# DCDCreg.net
KiCad netlist of a schematic drawn in Altium Designer
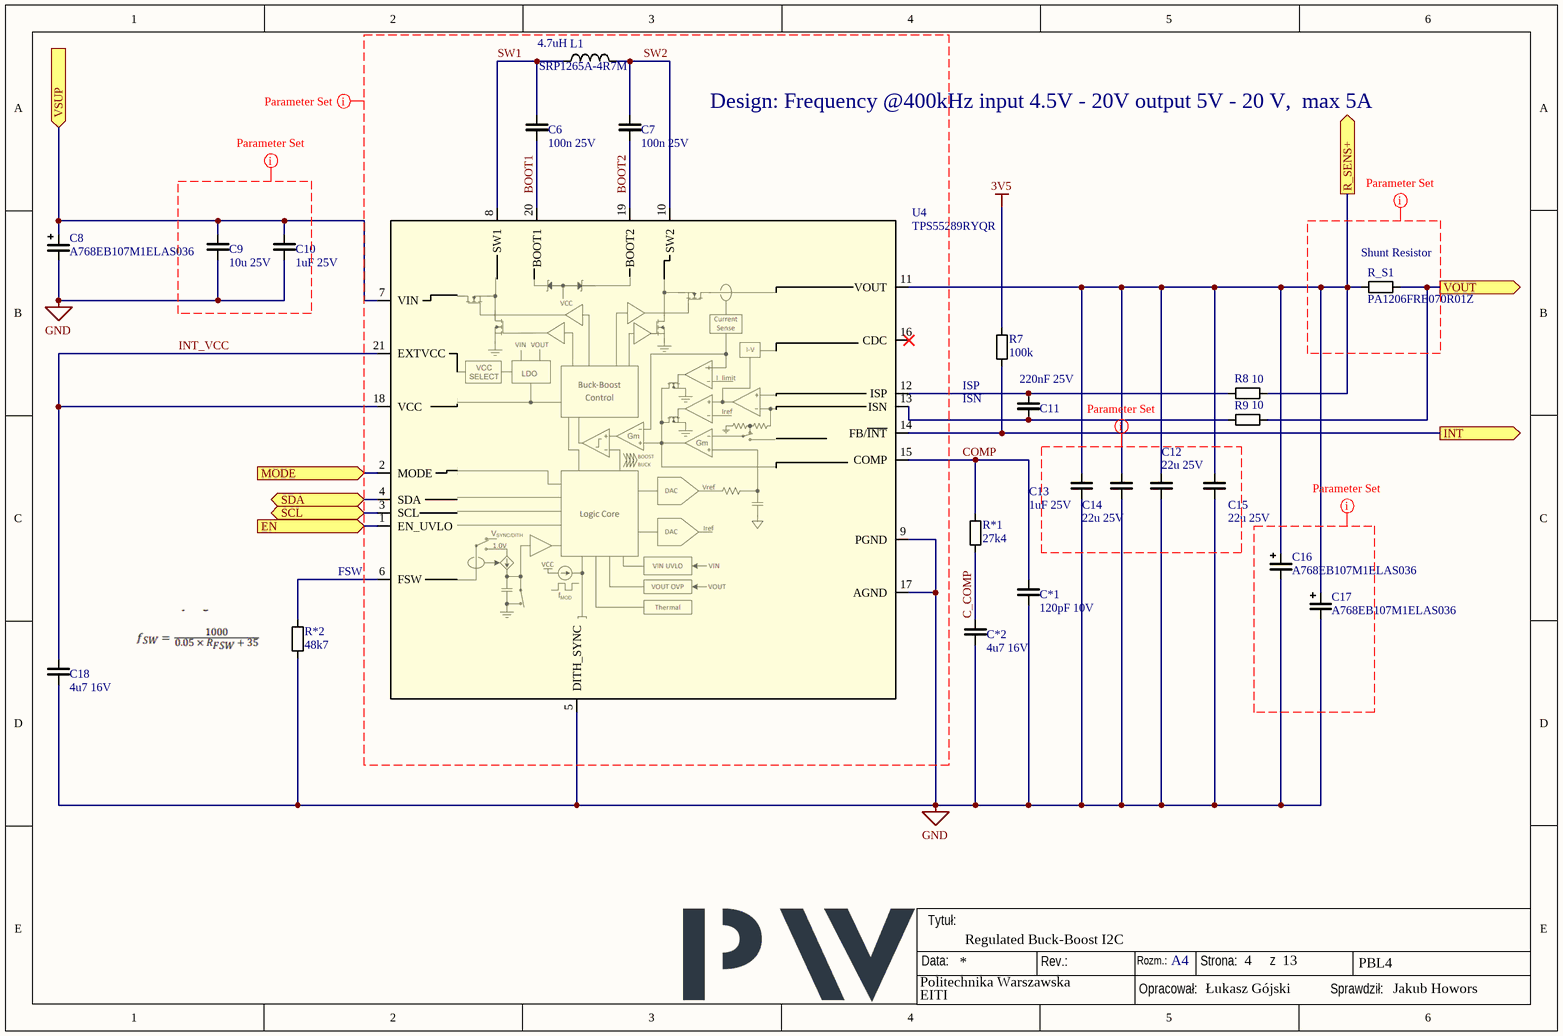
[diagram p0: DCDCreg.SchDoc]

(export (version "E")
  (design (tool "Eeschema 10.0.6"))
  (components
    (comp (ref "C*1")
      (value "120pF 10V")
      (footprint "C_0603")
      (description "Ceramic capacitor")
      (fields (field (name "VOLTAGE") "10V") (field (name "TOLERANCE") "10%"))
      (libsource (lib "Common") (part "C_120pF_10V"))
    )
    (comp (ref "C*2")
      (value "4u7 16V")
      (footprint "C_0603")
      (description "Ceramic capacitor")
      (fields (field (name "VOLTAGE") "16V") (field (name "TOLERANCE") "10%"))
      (libsource (lib "Common") (part "C_4u7_16V"))
    )
    (comp (ref "C6")
      (value "100n 25V")
      (footprint "C_0603")
      (description "Ceramic capacitor")
      (fields (field (name "VOLTAGE") "25V") (field (name "TOLERANCE") "10%"))
      (libsource (lib "Common") (part "C_100nF_25V"))
    )
    (comp (ref "C7")
      (value "100n 25V")
      (footprint "C_0603")
      (description "Ceramic capacitor")
      (fields (field (name "VOLTAGE") "25V") (field (name "TOLERANCE") "10%"))
      (libsource (lib "Common") (part "C_100nF_25V"))
    )
    (comp (ref "C8")
      (value "A768EB107M1ELAS036")
      (footprint "CAP_A768EB_6.8x6.8_KEM")
      (description "Aluminum Organic Polymer Capacitors 25Vol 100uF SMD 2KHr ESR=36 mOhms AECQ200")
      (fields (field (name "VOLTAGE") "25V") (field (name "TOLERANCE") "20%"))
      (libsource (lib "Common") (part "C_Pol_100uF_25V"))
    )
    (comp (ref "C9")
      (value "10u 25V")
      (footprint "C_0805")
      (description "Ceramic capacitor")
      (fields (field (name "VOLTAGE") "25V") (field (name "TOLERANCE") "10%"))
      (libsource (lib "Common") (part "C_10uF_25V"))
    )
    (comp (ref "C10")
      (value "1uF 25V")
      (footprint "C_0603")
      (description "Ceramic capacitor")
      (fields (field (name "VOLTAGE") "25V") (field (name "TOLERANCE") "10%"))
      (libsource (lib "Common") (part "C_1uF_25V"))
    )
    (comp (ref "C11")
      (value "220nF 25V")
      (footprint "C_0603")
      (description "Ceramic capacitor")
      (fields (field (name "VOLTAGE") "25V") (field (name "TOLERANCE") "10%"))
      (libsource (lib "Common") (part "C_220nF_25V"))
    )
    (comp (ref "C12")
      (value "22u 25V")
      (footprint "C_1206")
      (description "Ceramic capacitor")
      (fields (field (name "VOLTAGE") "25V") (field (name "TOLERANCE") "20%"))
      (libsource (lib "Common") (part "C_22uF_25V"))
    )
    (comp (ref "C13")
      (value "1uF 25V")
      (footprint "C_0603")
      (description "Ceramic capacitor")
      (fields (field (name "VOLTAGE") "25V") (field (name "TOLERANCE") "10%"))
      (libsource (lib "Common") (part "C_1uF_25V"))
    )
    (comp (ref "C14")
      (value "22u 25V")
      (footprint "C_1206")
      (description "Ceramic capacitor")
      (fields (field (name "VOLTAGE") "25V") (field (name "TOLERANCE") "20%"))
      (libsource (lib "Common") (part "C_22uF_25V"))
    )
    (comp (ref "C15")
      (value "22u 25V")
      (footprint "C_1206")
      (description "Ceramic capacitor")
      (fields (field (name "VOLTAGE") "25V") (field (name "TOLERANCE") "20%"))
      (libsource (lib "Common") (part "C_22uF_25V"))
    )
    (comp (ref "C16")
      (value "A768EB107M1ELAS036")
      (footprint "CAP_A768EB_6.8x6.8_KEM")
      (description "Aluminum Organic Polymer Capacitors 25Vol 100uF SMD 2KHr ESR=36 mOhms AECQ200")
      (fields (field (name "VOLTAGE") "25V") (field (name "TOLERANCE") "20%"))
      (libsource (lib "Common") (part "C_Pol_100uF_25V"))
    )
    (comp (ref "C17")
      (value "A768EB107M1ELAS036")
      (footprint "CAP_A768EB_6.8x6.8_KEM")
      (description "Aluminum Organic Polymer Capacitors 25Vol 100uF SMD 2KHr ESR=36 mOhms AECQ200")
      (fields (field (name "VOLTAGE") "25V") (field (name "TOLERANCE") "20%"))
      (libsource (lib "Common") (part "C_Pol_100uF_25V"))
    )
    (comp (ref "C18")
      (value "4u7 16V")
      (footprint "C_0603")
      (description "Ceramic capacitor")
      (fields (field (name "VOLTAGE") "16V") (field (name "TOLERANCE") "10%"))
      (libsource (lib "Common") (part "C_4u7_16V"))
    )
    (comp (ref "L1")
      (value "SRP1265A-4R7M")
      (footprint "SRP1265A-4R7M")
      (description "Inductor, 4.7 uF , 10A")
      (fields (field (name "TOLERANCE") "20%") (field (name "MANUFACTURER") "Bourns Inc."))
      (libsource (lib "PowerLib") (part "L_4u7_10.5A"))
    )
    (comp (ref "R*1")
      (value "27k4")
      (footprint "R_0603")
      (description "Resistor")
      (fields (field (name "TOLERANCE") "1%") (field (name "POWER") "100mW"))
      (libsource (lib "Common") (part "R_27k4"))
    )
    (comp (ref "R*2")
      (value "48k7")
      (footprint "R_0603")
      (description "Resistor")
      (fields (field (name "TOLERANCE") "1%") (field (name "POWER") "100mW"))
      (libsource (lib "Common") (part "R_48k7"))
    )
    (comp (ref "R7")
      (value "100k")
      (footprint "R_0603")
      (description "Resistor")
      (fields (field (name "TOLERANCE") "1%") (field (name "POWER") "100mW"))
      (libsource (lib "Common") (part "R_100k"))
    )
    (comp (ref "R8")
      (value "10")
      (footprint "R_0603")
      (fields (field (name "TOLERANCE") "1%") (field (name "POWER") "100mW"))
      (libsource (lib "Common") (part "R_10R"))
    )
    (comp (ref "R9")
      (value "10")
      (footprint "R_0603")
      (fields (field (name "TOLERANCE") "1%") (field (name "POWER") "100mW"))
      (libsource (lib "Common") (part "R_10R"))
    )
    (comp (ref "R_S1")
      (value "PA1206FRE070R01Z")
      (footprint "R_1206")
      (description "Shunt Resistor 10 mR, 1206, 250mW")
      (fields (field (name "TOLERANCE") "1%") (field (name "POWER") "250mW"))
      (libsource (lib "PowerLib") (part "R_10mR"))
    )
    (comp (ref "U4")
      (value "TPS55289RYQR")
      (footprint "RYQ0021A-MFG")
      (description "30-V, 8-A buck-boost converter with I2C interface")
      (fields (field (name "MANUFACTURER") "Texas Instruments"))
      (libsource (lib "PowerLib") (part "TPS55289RYQR"))
    )
  )
  (nets
    (net (code "1") (name "/BOOT1") (class "Default")
      (node (ref "C6") (pin "1") (pinfunction "1_1") (pintype "passive"))
      (node (ref "U4") (pin "20") (pinfunction "BOOT1_20") (pintype "passive"))
    )
    (net (code "2") (name "/BOOT2") (class "Default")
      (node (ref "C7") (pin "1") (pinfunction "1_1") (pintype "passive"))
      (node (ref "U4") (pin "19") (pinfunction "BOOT2_19") (pintype "passive"))
    )
    (net (code "3") (name "/COMP") (class "Default")
      (node (ref "C*1") (pin "2") (pinfunction "2_2") (pintype "passive"))
      (node (ref "R*1") (pin "2") (pinfunction "2_2") (pintype "passive"))
      (node (ref "U4") (pin "15") (pinfunction "COMP_15") (pintype "passive"))
    )
    (net (code "4") (name "/C_COMP") (class "Default")
      (node (ref "C*2") (pin "2") (pinfunction "2_2") (pintype "passive"))
      (node (ref "R*1") (pin "1") (pinfunction "1_1") (pintype "passive"))
    )
    (net (code "5") (name "/EN") (class "Default")
      (node (ref "U4") (pin "1") (pinfunction "EN_UVLO_1") (pintype "passive"))
    )
    (net (code "6") (name "/INT") (class "Default")
      (node (ref "R7") (pin "1") (pinfunction "1_1") (pintype "passive"))
      (node (ref "U4") (pin "14") (pinfunction "FB/~{INT}_14") (pintype "passive"))
    )
    (net (code "7") (name "/INT_VCC") (class "Default")
      (node (ref "C18") (pin "2") (pinfunction "2_2") (pintype "passive"))
      (node (ref "U4") (pin "18") (pinfunction "VCC_18") (pintype "power_in"))
      (node (ref "U4") (pin "21") (pinfunction "EXTVCC_21") (pintype "passive"))
    )
    (net (code "8") (name "/MODE") (class "Default")
      (node (ref "U4") (pin "2") (pinfunction "MODE_2") (pintype "passive"))
    )
    (net (code "9") (name "/R_SENS+") (class "Default")
      (node (ref "C12") (pin "2") (pinfunction "2_2") (pintype "passive"))
      (node (ref "C13") (pin "2") (pinfunction "2_2") (pintype "passive"))
      (node (ref "C14") (pin "2") (pinfunction "2_2") (pintype "passive"))
      (node (ref "C15") (pin "2") (pinfunction "2_2") (pintype "passive"))
      (node (ref "C16") (pin "1") (pinfunction "1_1") (pintype "passive"))
      (node (ref "C17") (pin "1") (pinfunction "1_1") (pintype "passive"))
      (node (ref "R8") (pin "1") (pinfunction "1_1") (pintype "passive"))
      (node (ref "R_S1") (pin "1") (pinfunction "1_1") (pintype "passive"))
      (node (ref "U4") (pin "11") (pinfunction "VOUT_11") (pintype "passive"))
    )
    (net (code "10") (name "/SCL") (class "Default")
      (node (ref "U4") (pin "3") (pinfunction "SCL_3") (pintype "passive"))
    )
    (net (code "11") (name "/SDA") (class "Default")
      (node (ref "U4") (pin "4") (pinfunction "SDA_4") (pintype "passive"))
    )
    (net (code "12") (name "/SW1") (class "Default")
      (node (ref "C6") (pin "2") (pinfunction "2_2") (pintype "passive"))
      (node (ref "L1") (pin "1") (pinfunction "1_1") (pintype "passive"))
      (node (ref "U4") (pin "8") (pinfunction "SW1_8") (pintype "passive"))
    )
    (net (code "13") (name "/SW2") (class "Default")
      (node (ref "C7") (pin "2") (pinfunction "2_2") (pintype "passive"))
      (node (ref "L1") (pin "2") (pinfunction "2_2") (pintype "passive"))
      (node (ref "U4") (pin "10") (pinfunction "SW2_10") (pintype "passive"))
    )
    (net (code "14") (name "/VOUT") (class "Default")
      (node (ref "R9") (pin "1") (pinfunction "1_1") (pintype "passive"))
      (node (ref "R_S1") (pin "2") (pinfunction "2_2") (pintype "passive"))
    )
    (net (code "15") (name "/VSUP") (class "Default")
      (node (ref "C10") (pin "2") (pinfunction "2_2") (pintype "passive"))
      (node (ref "C8") (pin "1") (pinfunction "1_1") (pintype "passive"))
      (node (ref "C9") (pin "2") (pinfunction "2_2") (pintype "passive"))
      (node (ref "U4") (pin "7") (pinfunction "VIN_7") (pintype "passive"))
    )
    (net (code "16") (name "3V5") (class "Default")
      (node (ref "R7") (pin "2") (pinfunction "2_2") (pintype "passive"))
    )
    (net (code "17") (name "GND") (class "Default")
      (node (ref "C*1") (pin "1") (pinfunction "1_1") (pintype "passive"))
      (node (ref "C*2") (pin "1") (pinfunction "1_1") (pintype "passive"))
      (node (ref "C10") (pin "1") (pinfunction "1_1") (pintype "passive"))
      (node (ref "C12") (pin "1") (pinfunction "1_1") (pintype "passive"))
      (node (ref "C13") (pin "1") (pinfunction "1_1") (pintype "passive"))
      (node (ref "C14") (pin "1") (pinfunction "1_1") (pintype "passive"))
      (node (ref "C15") (pin "1") (pinfunction "1_1") (pintype "passive"))
      (node (ref "C16") (pin "2") (pinfunction "2_2") (pintype "passive"))
      (node (ref "C17") (pin "2") (pinfunction "2_2") (pintype "passive"))
      (node (ref "C18") (pin "1") (pinfunction "1_1") (pintype "passive"))
      (node (ref "C8") (pin "2") (pinfunction "2_2") (pintype "passive"))
      (node (ref "C9") (pin "1") (pinfunction "1_1") (pintype "passive"))
      (node (ref "R*2") (pin "1") (pinfunction "1_1") (pintype "passive"))
      (node (ref "U4") (pin "17") (pinfunction "AGND_17") (pintype "power_in"))
      (node (ref "U4") (pin "5") (pinfunction "DITH_SYNC_5") (pintype "passive"))
      (node (ref "U4") (pin "9") (pinfunction "PGND_9") (pintype "power_in"))
    )
    (net (code "18") (name "Net-(U4-FSW)") (class "Default")
      (node (ref "R*2") (pin "2") (pinfunction "2_2") (pintype "passive"))
      (node (ref "U4") (pin "6") (pinfunction "FSW_6") (pintype "passive"))
    )
    (net (code "19") (name "Net-(U4-ISN)") (class "Default")
      (node (ref "C11") (pin "1") (pinfunction "1_1") (pintype "passive"))
      (node (ref "R9") (pin "2") (pinfunction "2_2") (pintype "passive"))
      (node (ref "U4") (pin "13") (pinfunction "ISN_13") (pintype "passive"))
    )
    (net (code "20") (name "Net-(U4-ISP)") (class "Default")
      (node (ref "C11") (pin "2") (pinfunction "2_2") (pintype "passive"))
      (node (ref "R8") (pin "2") (pinfunction "2_2") (pintype "passive"))
      (node (ref "U4") (pin "12") (pinfunction "ISP_12") (pintype "passive"))
    )
    (net (code "21") (name "unconnected-(U4-CDC-Pad16)") (class "Default")
      (node (ref "U4") (pin "16") (pinfunction "CDC_16") (pintype "passive+no_connect"))
    )
  )
)
